# LSM6DSOX_Ctrl.net
KiCad netlist of a schematic drawn in Altium Designer
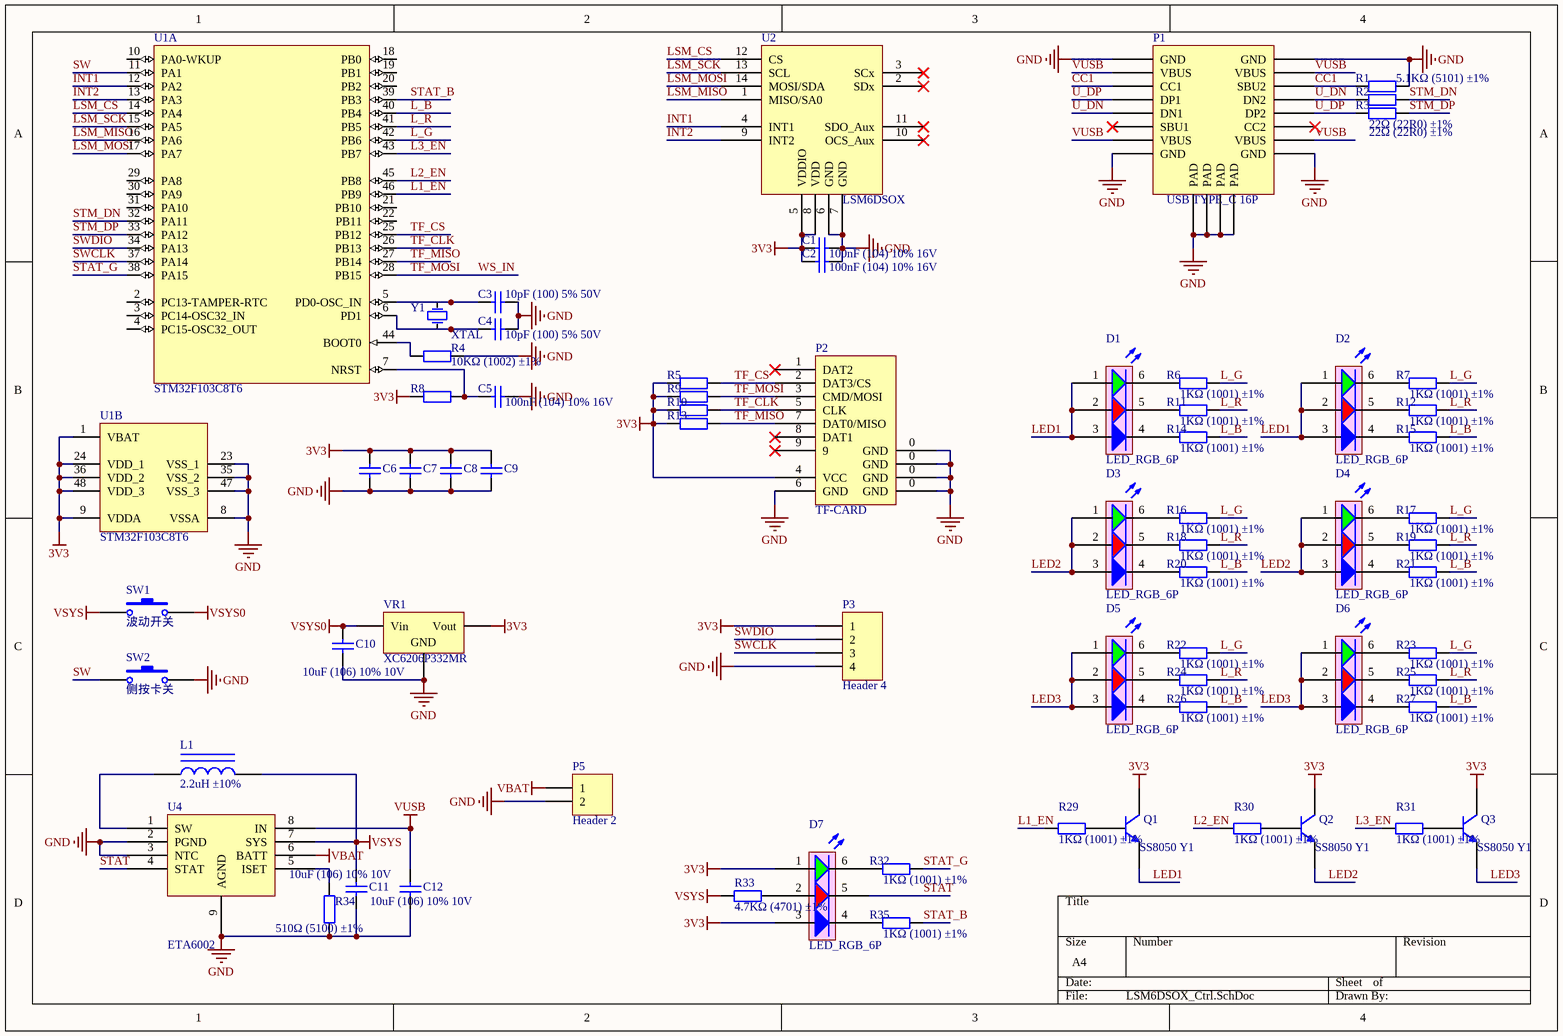
[diagram p0: LSM6DSOX_Ctrl.SchDoc]

(export (version "E")
  (design (tool "Eeschema 10.0.6"))
  (components
    (comp (ref "C1")
      (value "100nF (104) 10% 16V")
      (footprint "0402_C")
      (description "贴片电容")
      (libsource (lib "Miscellaneous Devices LC") (part "0402 100nF (104) 10% 16V"))
    )
    (comp (ref "C2")
      (value "100nF (104) 10% 16V")
      (footprint "0402_C")
      (description "贴片电容")
      (libsource (lib "Miscellaneous Devices LC") (part "0402 100nF (104) 10% 16V"))
    )
    (comp (ref "C3")
      (value "10pF (100) 5% 50V")
      (footprint "0402_C")
      (description "贴片电容")
      (libsource (lib "Miscellaneous Devices LC") (part "0402 10pF (100) 5% 50V"))
    )
    (comp (ref "C4")
      (value "10pF (100) 5% 50V")
      (footprint "0402_C")
      (description "贴片电容")
      (libsource (lib "Miscellaneous Devices LC") (part "0402 10pF (100) 5% 50V"))
    )
    (comp (ref "C5")
      (value "100nF (104) 10% 16V")
      (footprint "0402_C")
      (description "贴片电容")
      (libsource (lib "Miscellaneous Devices LC") (part "0402 100nF (104) 10% 16V"))
    )
    (comp (ref "C6")
      (value "100nF (104) 10% 16V")
      (footprint "0402_C")
      (description "贴片电容")
      (libsource (lib "Miscellaneous Devices LC") (part "0402 100nF (104) 10% 16V"))
    )
    (comp (ref "C7")
      (value "100nF (104) 10% 16V")
      (footprint "0402_C")
      (description "贴片电容")
      (libsource (lib "Miscellaneous Devices LC") (part "0402 100nF (104) 10% 16V"))
    )
    (comp (ref "C8")
      (value "100nF (104) 10% 16V")
      (footprint "0402_C")
      (description "贴片电容")
      (libsource (lib "Miscellaneous Devices LC") (part "0402 100nF (104) 10% 16V"))
    )
    (comp (ref "C9")
      (value "100nF (104) 10% 16V")
      (footprint "0402_C")
      (description "贴片电容")
      (libsource (lib "Miscellaneous Devices LC") (part "0402 100nF (104) 10% 16V"))
    )
    (comp (ref "C10")
      (value "10uF (106) 10% 10V")
      (footprint "0603_C")
      (description "贴片电容")
      (libsource (lib "Miscellaneous Devices LC") (part "0603 10uF (106) 10% 10V"))
    )
    (comp (ref "C11")
      (value "10uF (106) 10% 10V")
      (footprint "0603_C")
      (description "贴片电容")
      (libsource (lib "Miscellaneous Devices LC") (part "0603 10uF (106) 10% 10V"))
    )
    (comp (ref "C12")
      (value "10uF (106) 10% 10V")
      (footprint "0603_C")
      (description "贴片电容")
      (libsource (lib "Miscellaneous Devices LC") (part "0603 10uF (106) 10% 10V"))
    )
    (comp (ref "D1")
      (value "LED_RGB_6P")
      (footprint "LED_6P")
      (libsource (lib "Main_Ctr_SchLib") (part "LED_RGB_6P"))
    )
    (comp (ref "D2")
      (value "LED_RGB_6P")
      (footprint "LED_6P")
      (libsource (lib "Main_Ctr_SchLib") (part "LED_RGB_6P"))
    )
    (comp (ref "D3")
      (value "LED_RGB_6P")
      (footprint "LED_6P")
      (libsource (lib "Main_Ctr_SchLib") (part "LED_RGB_6P"))
    )
    (comp (ref "D4")
      (value "LED_RGB_6P")
      (footprint "LED_6P")
      (libsource (lib "Main_Ctr_SchLib") (part "LED_RGB_6P"))
    )
    (comp (ref "D5")
      (value "LED_RGB_6P")
      (footprint "LED_6P")
      (libsource (lib "Main_Ctr_SchLib") (part "LED_RGB_6P"))
    )
    (comp (ref "D6")
      (value "LED_RGB_6P")
      (footprint "LED_6P")
      (libsource (lib "Main_Ctr_SchLib") (part "LED_RGB_6P"))
    )
    (comp (ref "D7")
      (value "LED_RGB_6P")
      (footprint "LED_6P")
      (libsource (lib "Main_Ctr_SchLib") (part "LED_RGB_6P"))
    )
    (comp (ref "L1")
      (value "2.2uH ±10%")
      (footprint "0805_L")
      (description "贴片电感")
      (libsource (lib "Miscellaneous Devices LC") (part "0805 2.2uH 10%"))
    )
    (comp (ref "P1")
      (value "USB TYPE_C 16P")
      (footprint "USB-Typec 16P母")
      (description "USB Type_c 16p")
      (libsource (lib "Main_Ctr_SchLib") (part "USB TYPE_C 16P"))
    )
    (comp (ref "P2")
      (value "TF-CARD")
      (footprint "TF-1.7H")
      (description "TF卡槽")
      (libsource (lib "Main_Ctr_SchLib") (part "TF-CARD"))
    )
    (comp (ref "P3")
      (value "Header 4")
      (footprint "HDR1X4")
      (description "Header, 4-Pin")
      (fields (field (name "PUBLISHER") "Altium Limited"))
      (libsource (lib "Miscellaneous Connectors") (part "Header 4"))
    )
    (comp (ref "P5")
      (value "Header 2")
      (footprint "HDR1X2")
      (description "Header, 2-Pin")
      (fields (field (name "PUBLISHER") "Altium Limited"))
      (libsource (lib "Miscellaneous Connectors") (part "Header 2"))
    )
    (comp (ref "Q1")
      (value "SS8050 Y1")
      (footprint "SOT-23(SOT-23-3)")
      (description "三极管")
      (libsource (lib "Miscellaneous Devices LC") (part "SOT-23 SS8050 Y1"))
    )
    (comp (ref "Q2")
      (value "SS8050 Y1")
      (footprint "SOT-23(SOT-23-3)")
      (description "三极管")
      (libsource (lib "Miscellaneous Devices LC") (part "SOT-23 SS8050 Y1"))
    )
    (comp (ref "Q3")
      (value "SS8050 Y1")
      (footprint "SOT-23(SOT-23-3)")
      (description "三极管")
      (libsource (lib "Miscellaneous Devices LC") (part "SOT-23 SS8050 Y1"))
    )
    (comp (ref "R1")
      (value "5.1KΩ (5101) ±1%")
      (footprint "0402_R")
      (description "贴片电阻")
      (libsource (lib "Miscellaneous Devices LC") (part "0402 5.1KΩ (5101) 1%"))
    )
    (comp (ref "R2")
      (value "22Ω (22R0) ±1%")
      (footprint "0402_R")
      (description "贴片电阻")
      (libsource (lib "Miscellaneous Devices LC") (part "0402 22Ω (22R0) 1%"))
    )
    (comp (ref "R3")
      (value "22Ω (22R0) ±1%")
      (footprint "0402_R")
      (description "贴片电阻")
      (libsource (lib "Miscellaneous Devices LC") (part "0402 22Ω (22R0) 1%"))
    )
    (comp (ref "R4")
      (value "10KΩ (1002) ±1%")
      (footprint "0402_R")
      (description "贴片电阻")
      (libsource (lib "Miscellaneous Devices LC") (part "0402 10KΩ (1002) 1%"))
    )
    (comp (ref "R5")
      (value "10KΩ (1002) ±1%")
      (footprint "0402_R")
      (description "贴片电阻")
      (libsource (lib "Miscellaneous Devices LC") (part "0402 10KΩ (1002) 1%"))
    )
    (comp (ref "R6")
      (value "1KΩ (1001) ±1%")
      (footprint "0402_R")
      (description "贴片电阻")
      (libsource (lib "Miscellaneous Devices LC") (part "0402 1KΩ (1001) 1%"))
    )
    (comp (ref "R7")
      (value "1KΩ (1001) ±1%")
      (footprint "0402_R")
      (description "贴片电阻")
      (libsource (lib "Miscellaneous Devices LC") (part "0402 1KΩ (1001) 1%"))
    )
    (comp (ref "R8")
      (value "10KΩ (1002) ±1%")
      (footprint "0402_R")
      (description "贴片电阻")
      (libsource (lib "Miscellaneous Devices LC") (part "0402 10KΩ (1002) 1%"))
    )
    (comp (ref "R9")
      (value "10KΩ (1002) ±1%")
      (footprint "0402_R")
      (description "贴片电阻")
      (libsource (lib "Miscellaneous Devices LC") (part "0402 10KΩ (1002) 1%"))
    )
    (comp (ref "R10")
      (value "10KΩ (1002) ±1%")
      (footprint "0402_R")
      (description "贴片电阻")
      (libsource (lib "Miscellaneous Devices LC") (part "0402 10KΩ (1002) 1%"))
    )
    (comp (ref "R11")
      (value "1KΩ (1001) ±1%")
      (footprint "0402_R")
      (description "贴片电阻")
      (libsource (lib "Miscellaneous Devices LC") (part "0402 1KΩ (1001) 1%"))
    )
    (comp (ref "R12")
      (value "1KΩ (1001) ±1%")
      (footprint "0402_R")
      (description "贴片电阻")
      (libsource (lib "Miscellaneous Devices LC") (part "0402 1KΩ (1001) 1%"))
    )
    (comp (ref "R13")
      (value "10KΩ (1002) ±1%")
      (footprint "0402_R")
      (description "贴片电阻")
      (libsource (lib "Miscellaneous Devices LC") (part "0402 10KΩ (1002) 1%"))
    )
    (comp (ref "R14")
      (value "1KΩ (1001) ±1%")
      (footprint "0402_R")
      (description "贴片电阻")
      (libsource (lib "Miscellaneous Devices LC") (part "0402 1KΩ (1001) 1%"))
    )
    (comp (ref "R15")
      (value "1KΩ (1001) ±1%")
      (footprint "0402_R")
      (description "贴片电阻")
      (libsource (lib "Miscellaneous Devices LC") (part "0402 1KΩ (1001) 1%"))
    )
    (comp (ref "R16")
      (value "1KΩ (1001) ±1%")
      (footprint "0402_R")
      (description "贴片电阻")
      (libsource (lib "Miscellaneous Devices LC") (part "0402 1KΩ (1001) 1%"))
    )
    (comp (ref "R17")
      (value "1KΩ (1001) ±1%")
      (footprint "0402_R")
      (description "贴片电阻")
      (libsource (lib "Miscellaneous Devices LC") (part "0402 1KΩ (1001) 1%"))
    )
    (comp (ref "R18")
      (value "1KΩ (1001) ±1%")
      (footprint "0402_R")
      (description "贴片电阻")
      (libsource (lib "Miscellaneous Devices LC") (part "0402 1KΩ (1001) 1%"))
    )
    (comp (ref "R19")
      (value "1KΩ (1001) ±1%")
      (footprint "0402_R")
      (description "贴片电阻")
      (libsource (lib "Miscellaneous Devices LC") (part "0402 1KΩ (1001) 1%"))
    )
    (comp (ref "R20")
      (value "1KΩ (1001) ±1%")
      (footprint "0402_R")
      (description "贴片电阻")
      (libsource (lib "Miscellaneous Devices LC") (part "0402 1KΩ (1001) 1%"))
    )
    (comp (ref "R21")
      (value "1KΩ (1001) ±1%")
      (footprint "0402_R")
      (description "贴片电阻")
      (libsource (lib "Miscellaneous Devices LC") (part "0402 1KΩ (1001) 1%"))
    )
    (comp (ref "R22")
      (value "1KΩ (1001) ±1%")
      (footprint "0402_R")
      (description "贴片电阻")
      (libsource (lib "Miscellaneous Devices LC") (part "0402 1KΩ (1001) 1%"))
    )
    (comp (ref "R23")
      (value "1KΩ (1001) ±1%")
      (footprint "0402_R")
      (description "贴片电阻")
      (libsource (lib "Miscellaneous Devices LC") (part "0402 1KΩ (1001) 1%"))
    )
    (comp (ref "R24")
      (value "1KΩ (1001) ±1%")
      (footprint "0402_R")
      (description "贴片电阻")
      (libsource (lib "Miscellaneous Devices LC") (part "0402 1KΩ (1001) 1%"))
    )
    (comp (ref "R25")
      (value "1KΩ (1001) ±1%")
      (footprint "0402_R")
      (description "贴片电阻")
      (libsource (lib "Miscellaneous Devices LC") (part "0402 1KΩ (1001) 1%"))
    )
    (comp (ref "R26")
      (value "1KΩ (1001) ±1%")
      (footprint "0402_R")
      (description "贴片电阻")
      (libsource (lib "Miscellaneous Devices LC") (part "0402 1KΩ (1001) 1%"))
    )
    (comp (ref "R27")
      (value "1KΩ (1001) ±1%")
      (footprint "0402_R")
      (description "贴片电阻")
      (libsource (lib "Miscellaneous Devices LC") (part "0402 1KΩ (1001) 1%"))
    )
    (comp (ref "R29")
      (value "1KΩ (1001) ±1%")
      (footprint "0402_R")
      (description "贴片电阻")
      (libsource (lib "Miscellaneous Devices LC") (part "0402 1KΩ (1001) 1%"))
    )
    (comp (ref "R30")
      (value "1KΩ (1001) ±1%")
      (footprint "0402_R")
      (description "贴片电阻")
      (libsource (lib "Miscellaneous Devices LC") (part "0402 1KΩ (1001) 1%"))
    )
    (comp (ref "R31")
      (value "1KΩ (1001) ±1%")
      (footprint "0402_R")
      (description "贴片电阻")
      (libsource (lib "Miscellaneous Devices LC") (part "0402 1KΩ (1001) 1%"))
    )
    (comp (ref "R32")
      (value "1KΩ (1001) ±1%")
      (footprint "0402_R")
      (description "贴片电阻")
      (libsource (lib "Miscellaneous Devices LC") (part "0402 1KΩ (1001) 1%"))
    )
    (comp (ref "R33")
      (value "4.7KΩ (4701) ±1%")
      (footprint "0402_R")
      (description "贴片电阻")
      (libsource (lib "Miscellaneous Devices LC") (part "0402 4.7KΩ (4701) 1%"))
    )
    (comp (ref "R34")
      (value "510Ω (5100) ±1%")
      (footprint "0603_R")
      (description "贴片电阻")
      (libsource (lib "Miscellaneous Devices LC") (part "0603 510Ω (5100) 1%"))
    )
    (comp (ref "R35")
      (value "1KΩ (1001) ±1%")
      (footprint "0402_R")
      (description "贴片电阻")
      (libsource (lib "Miscellaneous Devices LC") (part "0402 1KΩ (1001) 1%"))
    )
    (comp (ref "SW1")
      (value "波动开关")
      (footprint "SW-SMD_3P-L6.6-W2.7-P1.50")
      (description "微动开关")
      (libsource (lib "Main_Ctr_SchLib") (part "SW"))
    )
    (comp (ref "SW2")
      (value "侧按卡关")
      (footprint "SW_PTCFG")
      (description "微动开关")
      (libsource (lib "Main_Ctr_SchLib") (part "SW"))
    )
    (comp (ref "U1")
      (value "STM32F103C8T6")
      (footprint "LQFP-48_7x7x05P")
      (description "ARM")
      (libsource (lib "Miscellaneous Devices LC") (part "STM32F103C8T6"))
    )
    (comp (ref "U2")
      (value "LSM6DSOX")
      (footprint "LGA-14L")
      (libsource (lib "Main_Ctr_SchLib") (part "LSM6DSOX"))
    )
    (comp (ref "U4")
      (value "ETA6002")
      (footprint "SOIC-8P")
      (description "3.7V充电芯片")
      (libsource (lib "Main_Ctr_SchLib") (part "ETA6002"))
    )
    (comp (ref "VR1")
      (value "XC6206P332MR")
      (footprint "SOT-23-3L")
      (description "低压差线性稳压(LDO)")
      (libsource (lib "Miscellaneous Devices LC") (part "SOT-23 XC6206P332MR"))
    )
    (comp (ref "Y1")
      (value "XTAL")
      (footprint "MURATA")
      (description "无源晶振")
      (libsource (lib "Main_Ctr_SchLib") (part "XTAL"))
    )
  )
  (nets
    (net (code "1") (name "/CC1") (class "Default")
      (node (ref "P1") (pin "A5") (pinfunction "CC1_A5") (pintype "passive"))
      (node (ref "P1") (pin "B8") (pinfunction "SBU2_B8") (pintype "passive"))
      (node (ref "R1") (pin "1") (pinfunction "1_1") (pintype "passive"))
    )
    (net (code "2") (name "/INT1") (class "Default")
      (node (ref "U1") (pin "12") (pinfunction "PA2_12") (pintype "bidirectional"))
      (node (ref "U2") (pin "4") (pinfunction "INT1_4") (pintype "passive"))
    )
    (net (code "3") (name "/INT2") (class "Default")
      (node (ref "U1") (pin "13") (pinfunction "PA3_13") (pintype "bidirectional"))
      (node (ref "U2") (pin "9") (pinfunction "INT2_9") (pintype "passive"))
    )
    (net (code "4") (name "/L1_EN") (class "Default")
      (node (ref "R29") (pin "1") (pinfunction "1_1") (pintype "passive"))
      (node (ref "U1") (pin "46") (pinfunction "PB9_46") (pintype "bidirectional"))
    )
    (net (code "5") (name "/L2_EN") (class "Default")
      (node (ref "R30") (pin "1") (pinfunction "1_1") (pintype "passive"))
      (node (ref "U1") (pin "45") (pinfunction "PB8_45") (pintype "bidirectional"))
    )
    (net (code "6") (name "/L3_EN") (class "Default")
      (node (ref "R31") (pin "1") (pinfunction "1_1") (pintype "passive"))
      (node (ref "U1") (pin "43") (pinfunction "PB7_43") (pintype "bidirectional"))
    )
    (net (code "7") (name "/LED1") (class "Default")
      (node (ref "D1") (pin "1") (pinfunction "A_G_1") (pintype "passive"))
      (node (ref "D1") (pin "2") (pinfunction "A_B_2") (pintype "passive"))
      (node (ref "D1") (pin "3") (pinfunction "A_R_3") (pintype "passive"))
      (node (ref "D2") (pin "1") (pinfunction "A_G_1") (pintype "passive"))
      (node (ref "D2") (pin "2") (pinfunction "A_B_2") (pintype "passive"))
      (node (ref "D2") (pin "3") (pinfunction "A_R_3") (pintype "passive"))
      (node (ref "Q1") (pin "2") (pinfunction "E_2") (pintype "passive"))
    )
    (net (code "8") (name "/LED2") (class "Default")
      (node (ref "D3") (pin "1") (pinfunction "A_G_1") (pintype "passive"))
      (node (ref "D3") (pin "2") (pinfunction "A_B_2") (pintype "passive"))
      (node (ref "D3") (pin "3") (pinfunction "A_R_3") (pintype "passive"))
      (node (ref "D4") (pin "1") (pinfunction "A_G_1") (pintype "passive"))
      (node (ref "D4") (pin "2") (pinfunction "A_B_2") (pintype "passive"))
      (node (ref "D4") (pin "3") (pinfunction "A_R_3") (pintype "passive"))
      (node (ref "Q2") (pin "2") (pinfunction "E_2") (pintype "passive"))
    )
    (net (code "9") (name "/LED3") (class "Default")
      (node (ref "D5") (pin "1") (pinfunction "A_G_1") (pintype "passive"))
      (node (ref "D5") (pin "2") (pinfunction "A_B_2") (pintype "passive"))
      (node (ref "D5") (pin "3") (pinfunction "A_R_3") (pintype "passive"))
      (node (ref "D6") (pin "1") (pinfunction "A_G_1") (pintype "passive"))
      (node (ref "D6") (pin "2") (pinfunction "A_B_2") (pintype "passive"))
      (node (ref "D6") (pin "3") (pinfunction "A_R_3") (pintype "passive"))
      (node (ref "Q3") (pin "2") (pinfunction "E_2") (pintype "passive"))
    )
    (net (code "10") (name "/LSM_CS") (class "Default")
      (node (ref "U1") (pin "14") (pinfunction "PA4_14") (pintype "bidirectional"))
      (node (ref "U2") (pin "12") (pinfunction "CS_12") (pintype "passive"))
    )
    (net (code "11") (name "/LSM_MISO") (class "Default")
      (node (ref "U1") (pin "16") (pinfunction "PA6_16") (pintype "bidirectional"))
      (node (ref "U2") (pin "1") (pinfunction "MISO/SA0_1") (pintype "passive"))
    )
    (net (code "12") (name "/LSM_MOSI") (class "Default")
      (node (ref "U1") (pin "17") (pinfunction "PA7_17") (pintype "bidirectional"))
      (node (ref "U2") (pin "14") (pinfunction "MOSI/SDA_14") (pintype "passive"))
    )
    (net (code "13") (name "/LSM_SCK") (class "Default")
      (node (ref "U1") (pin "15") (pinfunction "PA5_15") (pintype "bidirectional"))
      (node (ref "U2") (pin "13") (pinfunction "SCL_13") (pintype "passive"))
    )
    (net (code "14") (name "/L_B") (class "Default")
      (node (ref "R14") (pin "2") (pinfunction "2_2") (pintype "passive"))
      (node (ref "R15") (pin "2") (pinfunction "2_2") (pintype "passive"))
      (node (ref "R20") (pin "2") (pinfunction "2_2") (pintype "passive"))
      (node (ref "R21") (pin "2") (pinfunction "2_2") (pintype "passive"))
      (node (ref "R26") (pin "2") (pinfunction "2_2") (pintype "passive"))
      (node (ref "R27") (pin "2") (pinfunction "2_2") (pintype "passive"))
      (node (ref "U1") (pin "40") (pinfunction "PB4_40") (pintype "bidirectional"))
    )
    (net (code "15") (name "/L_G") (class "Default")
      (node (ref "R16") (pin "2") (pinfunction "2_2") (pintype "passive"))
      (node (ref "R17") (pin "2") (pinfunction "2_2") (pintype "passive"))
      (node (ref "R22") (pin "2") (pinfunction "2_2") (pintype "passive"))
      (node (ref "R23") (pin "2") (pinfunction "2_2") (pintype "passive"))
      (node (ref "R6") (pin "2") (pinfunction "2_2") (pintype "passive"))
      (node (ref "R7") (pin "2") (pinfunction "2_2") (pintype "passive"))
      (node (ref "U1") (pin "42") (pinfunction "PB6_42") (pintype "bidirectional"))
    )
    (net (code "16") (name "/L_R") (class "Default")
      (node (ref "R11") (pin "2") (pinfunction "2_2") (pintype "passive"))
      (node (ref "R12") (pin "2") (pinfunction "2_2") (pintype "passive"))
      (node (ref "R18") (pin "2") (pinfunction "2_2") (pintype "passive"))
      (node (ref "R19") (pin "2") (pinfunction "2_2") (pintype "passive"))
      (node (ref "R24") (pin "2") (pinfunction "2_2") (pintype "passive"))
      (node (ref "R25") (pin "2") (pinfunction "2_2") (pintype "passive"))
      (node (ref "U1") (pin "41") (pinfunction "PB5_41") (pintype "bidirectional"))
    )
    (net (code "17") (name "/STAT") (class "Default")
      (node (ref "D7") (pin "5") (pinfunction "B_5") (pintype "passive"))
      (node (ref "U4") (pin "4") (pinfunction "STAT_4") (pintype "passive"))
    )
    (net (code "18") (name "/STAT_B") (class "Default")
      (node (ref "R35") (pin "2") (pinfunction "2_2") (pintype "passive"))
      (node (ref "U1") (pin "39") (pinfunction "PB3_39") (pintype "bidirectional"))
    )
    (net (code "19") (name "/STAT_G") (class "Default")
      (node (ref "R32") (pin "2") (pinfunction "2_2") (pintype "passive"))
      (node (ref "U1") (pin "38") (pinfunction "PA15_38") (pintype "bidirectional"))
    )
    (net (code "20") (name "/STM_DN") (class "Default")
      (node (ref "R2") (pin "2") (pinfunction "2_2") (pintype "passive"))
      (node (ref "U1") (pin "32") (pinfunction "PA11_32") (pintype "bidirectional"))
    )
    (net (code "21") (name "/STM_DP") (class "Default")
      (node (ref "R3") (pin "2") (pinfunction "2_2") (pintype "passive"))
      (node (ref "U1") (pin "33") (pinfunction "PA12_33") (pintype "bidirectional"))
    )
    (net (code "22") (name "/SW") (class "Default")
      (node (ref "SW2") (pin "1") (pinfunction "1_1") (pintype "passive"))
      (node (ref "U1") (pin "11") (pinfunction "PA1_11") (pintype "bidirectional"))
    )
    (net (code "23") (name "/SWCLK") (class "Default")
      (node (ref "P3") (pin "3") (pinfunction "3_3") (pintype "passive"))
      (node (ref "U1") (pin "37") (pinfunction "PA14_37") (pintype "bidirectional"))
    )
    (net (code "24") (name "/SWDIO") (class "Default")
      (node (ref "P3") (pin "2") (pinfunction "2_2") (pintype "passive"))
      (node (ref "U1") (pin "34") (pinfunction "PA13_34") (pintype "bidirectional"))
    )
    (net (code "25") (name "/TF_CLK") (class "Default")
      (node (ref "P2") (pin "5") (pinfunction "CLK_5") (pintype "passive"))
      (node (ref "R10") (pin "2") (pinfunction "2_2") (pintype "passive"))
      (node (ref "U1") (pin "26") (pinfunction "PB13_26") (pintype "bidirectional"))
    )
    (net (code "26") (name "/TF_CS") (class "Default")
      (node (ref "P2") (pin "2") (pinfunction "DAT3/CS_2") (pintype "passive"))
      (node (ref "R5") (pin "2") (pinfunction "2_2") (pintype "passive"))
      (node (ref "U1") (pin "25") (pinfunction "PB12_25") (pintype "bidirectional"))
    )
    (net (code "27") (name "/TF_MISO") (class "Default")
      (node (ref "P2") (pin "7") (pinfunction "DAT0/MISO_7") (pintype "passive"))
      (node (ref "R13") (pin "2") (pinfunction "2_2") (pintype "passive"))
      (node (ref "U1") (pin "27") (pinfunction "PB14_27") (pintype "bidirectional"))
    )
    (net (code "28") (name "/TF_MOSI") (class "Default")
      (node (ref "P2") (pin "3") (pinfunction "CMD/MOSI_3") (pintype "passive"))
      (node (ref "R9") (pin "2") (pinfunction "2_2") (pintype "passive"))
      (node (ref "U1") (pin "28") (pinfunction "PB15_28") (pintype "bidirectional"))
    )
    (net (code "29") (name "/U_DN") (class "Default")
      (node (ref "P1") (pin "A7") (pinfunction "DN1_A7") (pintype "passive"))
      (node (ref "P1") (pin "B7") (pinfunction "DN2_B7") (pintype "passive"))
      (node (ref "R2") (pin "1") (pinfunction "1_1") (pintype "passive"))
    )
    (net (code "30") (name "/U_DP") (class "Default")
      (node (ref "P1") (pin "A6") (pinfunction "DP1_A6") (pintype "passive"))
      (node (ref "P1") (pin "B6") (pinfunction "DP2_B6") (pintype "passive"))
      (node (ref "R3") (pin "1") (pinfunction "1_1") (pintype "passive"))
    )
    (net (code "31") (name "3V3") (class "Default")
      (node (ref "C1") (pin "1") (pinfunction "1_1") (pintype "passive"))
      (node (ref "C2") (pin "1") (pinfunction "1_1") (pintype "passive"))
      (node (ref "C6") (pin "2") (pinfunction "2_2") (pintype "passive"))
      (node (ref "C7") (pin "2") (pinfunction "2_2") (pintype "passive"))
      (node (ref "C8") (pin "2") (pinfunction "2_2") (pintype "passive"))
      (node (ref "C9") (pin "2") (pinfunction "2_2") (pintype "passive"))
      (node (ref "D7") (pin "1") (pinfunction "A_G_1") (pintype "passive"))
      (node (ref "D7") (pin "3") (pinfunction "A_R_3") (pintype "passive"))
      (node (ref "P2") (pin "4") (pinfunction "VCC_4") (pintype "passive"))
      (node (ref "P3") (pin "1") (pinfunction "1_1") (pintype "passive"))
      (node (ref "Q1") (pin "3") (pinfunction "C_3") (pintype "passive"))
      (node (ref "Q2") (pin "3") (pinfunction "C_3") (pintype "passive"))
      (node (ref "Q3") (pin "3") (pinfunction "C_3") (pintype "passive"))
      (node (ref "R10") (pin "1") (pinfunction "1_1") (pintype "passive"))
      (node (ref "R13") (pin "1") (pinfunction "1_1") (pintype "passive"))
      (node (ref "R5") (pin "1") (pinfunction "1_1") (pintype "passive"))
      (node (ref "R8") (pin "1") (pinfunction "1_1") (pintype "passive"))
      (node (ref "R9") (pin "1") (pinfunction "1_1") (pintype "passive"))
      (node (ref "U1") (pin "1") (pinfunction "VBAT_1") (pintype "power_in"))
      (node (ref "U1") (pin "24") (pinfunction "VDD_1_24") (pintype "power_in"))
      (node (ref "U1") (pin "36") (pinfunction "VDD_2_36") (pintype "power_in"))
      (node (ref "U1") (pin "48") (pinfunction "VDD_3_48") (pintype "power_in"))
      (node (ref "U1") (pin "9") (pinfunction "VDDA_9") (pintype "power_in"))
      (node (ref "U2") (pin "5") (pinfunction "VDDIO_5") (pintype "passive"))
      (node (ref "U2") (pin "8") (pinfunction "VDD_8") (pintype "passive"))
      (node (ref "VR1") (pin "2") (pinfunction "Vout_2") (pintype "passive"))
    )
    (net (code "32") (name "GND") (class "Default")
      (node (ref "C1") (pin "2") (pinfunction "2_2") (pintype "passive"))
      (node (ref "C10") (pin "1") (pinfunction "1_1") (pintype "passive"))
      (node (ref "C11") (pin "1") (pinfunction "1_1") (pintype "passive"))
      (node (ref "C12") (pin "1") (pinfunction "1_1") (pintype "passive"))
      (node (ref "C2") (pin "2") (pinfunction "2_2") (pintype "passive"))
      (node (ref "C3") (pin "2") (pinfunction "2_2") (pintype "passive"))
      (node (ref "C4") (pin "1") (pinfunction "1_1") (pintype "passive"))
      (node (ref "C5") (pin "2") (pinfunction "2_2") (pintype "passive"))
      (node (ref "C6") (pin "1") (pinfunction "1_1") (pintype "passive"))
      (node (ref "C7") (pin "1") (pinfunction "1_1") (pintype "passive"))
      (node (ref "C8") (pin "1") (pinfunction "1_1") (pintype "passive"))
      (node (ref "C9") (pin "1") (pinfunction "1_1") (pintype "passive"))
      (node (ref "P1") (pin "1") (pinfunction "PAD_1") (pintype "passive"))
      (node (ref "P1") (pin "2") (pinfunction "PAD_2") (pintype "passive"))
      (node (ref "P1") (pin "3") (pinfunction "PAD_3") (pintype "passive"))
      (node (ref "P1") (pin "4") (pinfunction "PAD_4") (pintype "passive"))
      (node (ref "P1") (pin "A1") (pinfunction "GND_A1") (pintype "passive"))
      (node (ref "P1") (pin "A12") (pinfunction "GND_A12") (pintype "passive"))
      (node (ref "P1") (pin "B1") (pinfunction "GND_B1") (pintype "passive"))
      (node (ref "P1") (pin "B12") (pinfunction "GND_B12") (pintype "passive"))
      (node (ref "P2") (pin "0") (pinfunction "GND_0") (pintype "passive"))
      (node (ref "P2") (pin "6") (pinfunction "GND_6") (pintype "passive"))
      (node (ref "P3") (pin "4") (pinfunction "4_4") (pintype "passive"))
      (node (ref "P5") (pin "2") (pinfunction "2_2") (pintype "passive"))
      (node (ref "R1") (pin "2") (pinfunction "2_2") (pintype "passive"))
      (node (ref "R34") (pin "1") (pinfunction "1_1") (pintype "passive"))
      (node (ref "R4") (pin "2") (pinfunction "2_2") (pintype "passive"))
      (node (ref "SW2") (pin "2") (pinfunction "2_2") (pintype "passive"))
      (node (ref "U1") (pin "23") (pinfunction "VSS_1_23") (pintype "power_in"))
      (node (ref "U1") (pin "35") (pinfunction "VSS_2_35") (pintype "power_in"))
      (node (ref "U1") (pin "47") (pinfunction "VSS_3_47") (pintype "power_in"))
      (node (ref "U1") (pin "8") (pinfunction "VSSA_8") (pintype "power_in"))
      (node (ref "U2") (pin "6") (pinfunction "GND_6") (pintype "passive"))
      (node (ref "U2") (pin "7") (pinfunction "GND_7") (pintype "passive"))
      (node (ref "U4") (pin "2") (pinfunction "PGND_2") (pintype "passive"))
      (node (ref "U4") (pin "3") (pinfunction "NTC_3") (pintype "passive"))
      (node (ref "U4") (pin "9") (pinfunction "AGND_9") (pintype "passive"))
      (node (ref "VR1") (pin "1") (pinfunction "GND_1") (pintype "passive"))
    )
    (net (code "33") (name "Net-(D1-B)") (class "Default")
      (node (ref "D1") (pin "5") (pinfunction "B_5") (pintype "passive"))
      (node (ref "R11") (pin "1") (pinfunction "1_1") (pintype "passive"))
    )
    (net (code "34") (name "Net-(D1-G)") (class "Default")
      (node (ref "D1") (pin "6") (pinfunction "G_6") (pintype "passive"))
      (node (ref "R6") (pin "1") (pinfunction "1_1") (pintype "passive"))
    )
    (net (code "35") (name "Net-(D1-R)") (class "Default")
      (node (ref "D1") (pin "4") (pinfunction "R_4") (pintype "passive"))
      (node (ref "R14") (pin "1") (pinfunction "1_1") (pintype "passive"))
    )
    (net (code "36") (name "Net-(D2-B)") (class "Default")
      (node (ref "D2") (pin "5") (pinfunction "B_5") (pintype "passive"))
      (node (ref "R12") (pin "1") (pinfunction "1_1") (pintype "passive"))
    )
    (net (code "37") (name "Net-(D2-G)") (class "Default")
      (node (ref "D2") (pin "6") (pinfunction "G_6") (pintype "passive"))
      (node (ref "R7") (pin "1") (pinfunction "1_1") (pintype "passive"))
    )
    (net (code "38") (name "Net-(D2-R)") (class "Default")
      (node (ref "D2") (pin "4") (pinfunction "R_4") (pintype "passive"))
      (node (ref "R15") (pin "1") (pinfunction "1_1") (pintype "passive"))
    )
    (net (code "39") (name "Net-(D3-B)") (class "Default")
      (node (ref "D3") (pin "5") (pinfunction "B_5") (pintype "passive"))
      (node (ref "R18") (pin "1") (pinfunction "1_1") (pintype "passive"))
    )
    (net (code "40") (name "Net-(D3-G)") (class "Default")
      (node (ref "D3") (pin "6") (pinfunction "G_6") (pintype "passive"))
      (node (ref "R16") (pin "1") (pinfunction "1_1") (pintype "passive"))
    )
    (net (code "41") (name "Net-(D3-R)") (class "Default")
      (node (ref "D3") (pin "4") (pinfunction "R_4") (pintype "passive"))
      (node (ref "R20") (pin "1") (pinfunction "1_1") (pintype "passive"))
    )
    (net (code "42") (name "Net-(D4-B)") (class "Default")
      (node (ref "D4") (pin "5") (pinfunction "B_5") (pintype "passive"))
      (node (ref "R19") (pin "1") (pinfunction "1_1") (pintype "passive"))
    )
    (net (code "43") (name "Net-(D4-G)") (class "Default")
      (node (ref "D4") (pin "6") (pinfunction "G_6") (pintype "passive"))
      (node (ref "R17") (pin "1") (pinfunction "1_1") (pintype "passive"))
    )
    (net (code "44") (name "Net-(D4-R)") (class "Default")
      (node (ref "D4") (pin "4") (pinfunction "R_4") (pintype "passive"))
      (node (ref "R21") (pin "1") (pinfunction "1_1") (pintype "passive"))
    )
    (net (code "45") (name "Net-(D5-B)") (class "Default")
      (node (ref "D5") (pin "5") (pinfunction "B_5") (pintype "passive"))
      (node (ref "R24") (pin "1") (pinfunction "1_1") (pintype "passive"))
    )
    (net (code "46") (name "Net-(D5-G)") (class "Default")
      (node (ref "D5") (pin "6") (pinfunction "G_6") (pintype "passive"))
      (node (ref "R22") (pin "1") (pinfunction "1_1") (pintype "passive"))
    )
    (net (code "47") (name "Net-(D5-R)") (class "Default")
      (node (ref "D5") (pin "4") (pinfunction "R_4") (pintype "passive"))
      (node (ref "R26") (pin "1") (pinfunction "1_1") (pintype "passive"))
    )
    (net (code "48") (name "Net-(D6-B)") (class "Default")
      (node (ref "D6") (pin "5") (pinfunction "B_5") (pintype "passive"))
      (node (ref "R25") (pin "1") (pinfunction "1_1") (pintype "passive"))
    )
    (net (code "49") (name "Net-(D6-G)") (class "Default")
      (node (ref "D6") (pin "6") (pinfunction "G_6") (pintype "passive"))
      (node (ref "R23") (pin "1") (pinfunction "1_1") (pintype "passive"))
    )
    (net (code "50") (name "Net-(D6-R)") (class "Default")
      (node (ref "D6") (pin "4") (pinfunction "R_4") (pintype "passive"))
      (node (ref "R27") (pin "1") (pinfunction "1_1") (pintype "passive"))
    )
    (net (code "51") (name "Net-(D7-A_B)") (class "Default")
      (node (ref "D7") (pin "2") (pinfunction "A_B_2") (pintype "passive"))
      (node (ref "R33") (pin "2") (pinfunction "2_2") (pintype "passive"))
    )
    (net (code "52") (name "Net-(D7-G)") (class "Default")
      (node (ref "D7") (pin "6") (pinfunction "G_6") (pintype "passive"))
      (node (ref "R32") (pin "1") (pinfunction "1_1") (pintype "passive"))
    )
    (net (code "53") (name "Net-(D7-R)") (class "Default")
      (node (ref "D7") (pin "4") (pinfunction "R_4") (pintype "passive"))
      (node (ref "R35") (pin "1") (pinfunction "1_1") (pintype "passive"))
    )
    (net (code "54") (name "Net-(Q1-B)") (class "Default")
      (node (ref "Q1") (pin "1") (pinfunction "B_1") (pintype "passive"))
      (node (ref "R29") (pin "2") (pinfunction "2_2") (pintype "passive"))
    )
    (net (code "55") (name "Net-(Q2-B)") (class "Default")
      (node (ref "Q2") (pin "1") (pinfunction "B_1") (pintype "passive"))
      (node (ref "R30") (pin "2") (pinfunction "2_2") (pintype "passive"))
    )
    (net (code "56") (name "Net-(Q3-B)") (class "Default")
      (node (ref "Q3") (pin "1") (pinfunction "B_1") (pintype "passive"))
      (node (ref "R31") (pin "2") (pinfunction "2_2") (pintype "passive"))
    )
    (net (code "57") (name "Net-(U1A-BOOT0)") (class "Default")
      (node (ref "R4") (pin "1") (pinfunction "1_1") (pintype "passive"))
      (node (ref "U1") (pin "44") (pinfunction "BOOT0_44") (pintype "input"))
    )
    (net (code "58") (name "Net-(U1A-NRST)") (class "Default")
      (node (ref "C5") (pin "1") (pinfunction "1_1") (pintype "passive"))
      (node (ref "R8") (pin "2") (pinfunction "2_2") (pintype "passive"))
      (node (ref "U1") (pin "7") (pinfunction "NRST_7") (pintype "bidirectional"))
    )
    (net (code "59") (name "Net-(U1A-PD0-OSC_IN)") (class "Default")
      (node (ref "C3") (pin "1") (pinfunction "1_1") (pintype "passive"))
      (node (ref "U1") (pin "5") (pinfunction "PD0-OSC_IN_5") (pintype "bidirectional"))
      (node (ref "Y1") (pin "2") (pinfunction "OSC2_2") (pintype "passive"))
    )
    (net (code "60") (name "Net-(U1A-PD1)") (class "Default")
      (node (ref "C4") (pin "2") (pinfunction "2_2") (pintype "passive"))
      (node (ref "U1") (pin "6") (pinfunction "PD1_6") (pintype "bidirectional"))
      (node (ref "Y1") (pin "1") (pinfunction "OSC1_1") (pintype "passive"))
    )
    (net (code "61") (name "Net-(U4-ISET)") (class "Default")
      (node (ref "R34") (pin "2") (pinfunction "2_2") (pintype "passive"))
      (node (ref "U4") (pin "5") (pinfunction "ISET_5") (pintype "passive"))
    )
    (net (code "62") (name "Net-(U4-SW)") (class "Default")
      (node (ref "L1") (pin "1") (pinfunction "1_1") (pintype "passive"))
      (node (ref "U4") (pin "1") (pinfunction "SW_1") (pintype "passive"))
    )
    (net (code "63") (name "VBAT") (class "Default")
      (node (ref "P5") (pin "1") (pinfunction "1_1") (pintype "passive"))
      (node (ref "U4") (pin "6") (pinfunction "BATT_6") (pintype "passive"))
    )
    (net (code "64") (name "VSYS") (class "Default")
      (node (ref "C11") (pin "2") (pinfunction "2_2") (pintype "passive"))
      (node (ref "L1") (pin "2") (pinfunction "2_2") (pintype "passive"))
      (node (ref "R33") (pin "1") (pinfunction "1_1") (pintype "passive"))
      (node (ref "SW1") (pin "1") (pinfunction "1_1") (pintype "passive"))
      (node (ref "U4") (pin "7") (pinfunction "SYS_7") (pintype "passive"))
    )
    (net (code "65") (name "VSYS0") (class "Default")
      (node (ref "C10") (pin "2") (pinfunction "2_2") (pintype "passive"))
      (node (ref "SW1") (pin "2") (pinfunction "2_2") (pintype "passive"))
      (node (ref "VR1") (pin "3") (pinfunction "Vin_3") (pintype "passive"))
    )
    (net (code "66") (name "VUSB") (class "Default")
      (node (ref "C12") (pin "2") (pinfunction "2_2") (pintype "passive"))
      (node (ref "P1") (pin "A4") (pinfunction "VBUS_A4") (pintype "passive"))
      (node (ref "P1") (pin "A9") (pinfunction "VBUS_A9") (pintype "passive"))
      (node (ref "P1") (pin "B4") (pinfunction "VBUS_B4") (pintype "passive"))
      (node (ref "P1") (pin "B9") (pinfunction "VBUS_B9") (pintype "passive"))
      (node (ref "U4") (pin "8") (pinfunction "IN_8") (pintype "passive"))
    )
    (net (code "67") (name "unconnected-(P1-CC2-PadB5)") (class "Default")
      (node (ref "P1") (pin "B5") (pinfunction "CC2_B5") (pintype "passive+no_connect"))
    )
    (net (code "68") (name "unconnected-(P1-SBU1-PadA8)") (class "Default")
      (node (ref "P1") (pin "A8") (pinfunction "SBU1_A8") (pintype "passive+no_connect"))
    )
    (net (code "69") (name "unconnected-(P2-DAT1-Pad8)") (class "Default")
      (node (ref "P2") (pin "8") (pinfunction "DAT1_8") (pintype "passive+no_connect"))
    )
    (net (code "70") (name "unconnected-(P2-DAT2-Pad1)") (class "Default")
      (node (ref "P2") (pin "1") (pinfunction "DAT2_1") (pintype "passive+no_connect"))
    )
    (net (code "71") (name "unconnected-(P2-Pad9)") (class "Default")
      (node (ref "P2") (pin "9") (pinfunction "9_9") (pintype "passive+no_connect"))
    )
    (net (code "72") (name "unconnected-(U1A-PA0-WKUP-Pad10)") (class "Default")
      (node (ref "U1") (pin "10") (pinfunction "PA0-WKUP_10") (pintype "bidirectional"))
    )
    (net (code "73") (name "unconnected-(U1A-PA8-Pad29)") (class "Default")
      (node (ref "U1") (pin "29") (pinfunction "PA8_29") (pintype "bidirectional"))
    )
    (net (code "74") (name "unconnected-(U1A-PA9-Pad30)") (class "Default")
      (node (ref "U1") (pin "30") (pinfunction "PA9_30") (pintype "bidirectional"))
    )
    (net (code "75") (name "unconnected-(U1A-PA10-Pad31)") (class "Default")
      (node (ref "U1") (pin "31") (pinfunction "PA10_31") (pintype "bidirectional"))
    )
    (net (code "76") (name "unconnected-(U1A-PB0-Pad18)") (class "Default")
      (node (ref "U1") (pin "18") (pinfunction "PB0_18") (pintype "bidirectional"))
    )
    (net (code "77") (name "unconnected-(U1A-PB1-Pad19)") (class "Default")
      (node (ref "U1") (pin "19") (pinfunction "PB1_19") (pintype "bidirectional"))
    )
    (net (code "78") (name "unconnected-(U1A-PB2-Pad20)") (class "Default")
      (node (ref "U1") (pin "20") (pinfunction "PB2_20") (pintype "bidirectional"))
    )
    (net (code "79") (name "unconnected-(U1A-PB10-Pad21)") (class "Default")
      (node (ref "U1") (pin "21") (pinfunction "PB10_21") (pintype "bidirectional"))
    )
    (net (code "80") (name "unconnected-(U1A-PB11-Pad22)") (class "Default")
      (node (ref "U1") (pin "22") (pinfunction "PB11_22") (pintype "bidirectional"))
    )
    (net (code "81") (name "unconnected-(U1A-PC13-TAMPER-RTC-Pad2)") (class "Default")
      (node (ref "U1") (pin "2") (pinfunction "PC13-TAMPER-RTC_2") (pintype "bidirectional"))
    )
    (net (code "82") (name "unconnected-(U1A-PC14-OSC32_IN-Pad3)") (class "Default")
      (node (ref "U1") (pin "3") (pinfunction "PC14-OSC32_IN_3") (pintype "bidirectional"))
    )
    (net (code "83") (name "unconnected-(U1A-PC15-OSC32_OUT-Pad4)") (class "Default")
      (node (ref "U1") (pin "4") (pinfunction "PC15-OSC32_OUT_4") (pintype "bidirectional"))
    )
    (net (code "84") (name "unconnected-(U2-OCS_Aux-Pad10)") (class "Default")
      (node (ref "U2") (pin "10") (pinfunction "OCS_Aux_10") (pintype "passive+no_connect"))
    )
    (net (code "85") (name "unconnected-(U2-SCx-Pad3)") (class "Default")
      (node (ref "U2") (pin "3") (pinfunction "SCx_3") (pintype "passive+no_connect"))
    )
    (net (code "86") (name "unconnected-(U2-SDO_Aux-Pad11)") (class "Default")
      (node (ref "U2") (pin "11") (pinfunction "SDO_Aux_11") (pintype "passive+no_connect"))
    )
    (net (code "87") (name "unconnected-(U2-SDx-Pad2)") (class "Default")
      (node (ref "U2") (pin "2") (pinfunction "SDx_2") (pintype "passive+no_connect"))
    )
  )
)
